# Leds.net
KiCad netlist of a schematic drawn in Altium Designer
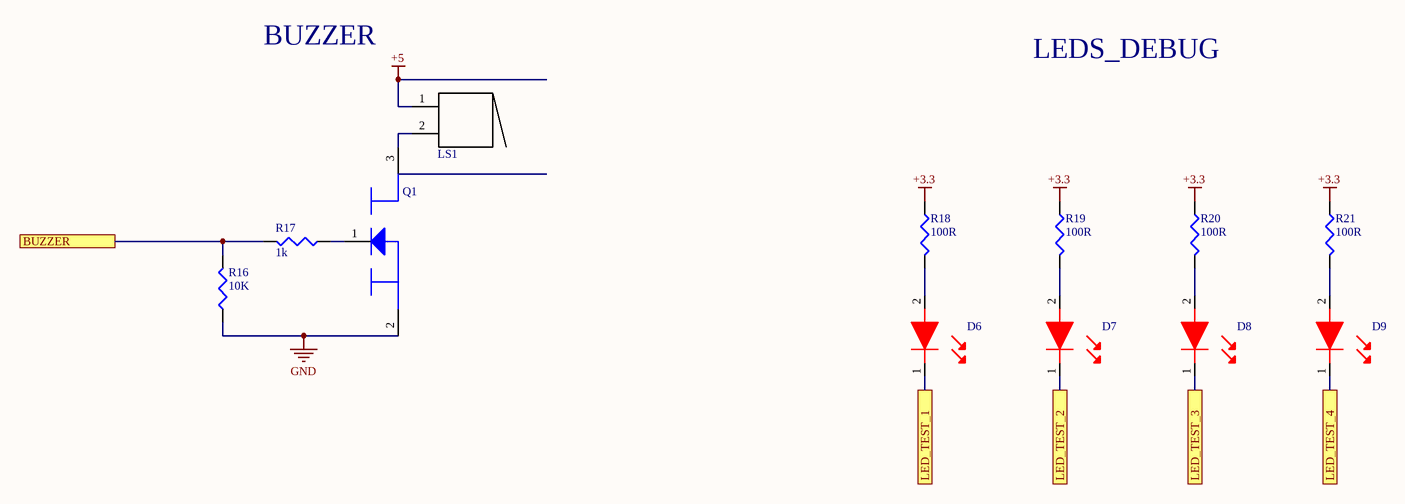
[diagram p0: Leds.SchDoc]

(export (version "E")
  (design (tool "Eeschema 10.0.6"))
  (components
    (comp (ref "D6")
      (value "Standard LEDs - SMD")
      (footprint "Standard LEDs - SMD")
      (description "WURTH ELEKTRONIK - 150060RS75000 - LED, 0603, RED, 250MCD, 625NM")
      (fields
        (field (name "MANUFACTURER") "Wurth Electronics")
        (field (name "MANUFACTURER PART NUMBER") "150060RS75000")
      )
      (libsource (lib "BiricuticoBonito") (part "Standard LEDs - SMD"))
    )
    (comp (ref "D7")
      (value "Standard LEDs - SMD")
      (footprint "Standard LEDs - SMD")
      (description "WURTH ELEKTRONIK - 150060RS75000 - LED, 0603, RED, 250MCD, 625NM")
      (fields
        (field (name "MANUFACTURER") "Wurth Electronics")
        (field (name "MANUFACTURER PART NUMBER") "150060RS75000")
      )
      (libsource (lib "BiricuticoBonito") (part "Standard LEDs - SMD"))
    )
    (comp (ref "D8")
      (value "Standard LEDs - SMD")
      (footprint "Standard LEDs - SMD")
      (description "WURTH ELEKTRONIK - 150060RS75000 - LED, 0603, RED, 250MCD, 625NM")
      (fields
        (field (name "MANUFACTURER") "Wurth Electronics")
        (field (name "MANUFACTURER PART NUMBER") "150060RS75000")
      )
      (libsource (lib "BiricuticoBonito") (part "Standard LEDs - SMD"))
    )
    (comp (ref "D9")
      (value "Standard LEDs - SMD")
      (footprint "Standard LEDs - SMD")
      (description "WURTH ELEKTRONIK - 150060RS75000 - LED, 0603, RED, 250MCD, 625NM")
      (fields
        (field (name "MANUFACTURER") "Wurth Electronics")
        (field (name "MANUFACTURER PART NUMBER") "150060RS75000")
      )
      (libsource (lib "BiricuticoBonito") (part "Standard LEDs - SMD"))
    )
    (comp (ref "LS1")
      (value "Buzzers")
      (footprint "Buzzer")
      (description "Audio 1.1Vp-p 3Vp-p 30mA 1.5Vp-p 85dBA 2400Hz to 2800Hz Through Hole Pin Bulk")
      (fields
        (field (name "MANUFACTURER") "Mallory Sonalert")
        (field (name "MANUFACTURER PART NUMBER") "PB-1226PEAQ")
      )
      (libsource (lib "BiricuticoBonito") (part "Buzzers"))
    )
    (comp (ref "Q1")
      (value "MOSFET")
      (footprint "SOT96P240X110-3N")
      (description "MOSFET N-CH 30V 6.2A SOT23")
      (fields (field (name "MANUFACTURER") "Diodes") (field (name "MANUFACTURER PART NUMBER") "DMN3023L-7"))
      (libsource (lib "BiricuticoBonito") (part "MOSFET"))
    )
    (comp (ref "R16")
      (value "10K")
      (footprint "6-0805_M")
      (description "RES SMD 10K OHM 1% 1/8W 0805")
      (fields
        (field (name "MANUFACTURER") "Vishay")
        (field (name "MANUFACTURER PART NUMBER") "CRCW080510K0FKEA")
      )
      (libsource (lib "BiricuticoBonito") (part "Resistor 10k 0805"))
    )
    (comp (ref "R17")
      (value "1k")
      (footprint "6-0805_M")
      (description "RES SMD 1K OHM 1% 1/8W 0805")
      (fields
        (field (name "MANUFACTURER") "Vishay Dale")
        (field (name "MANUFACTURER PART NUMBER") "CRCW08051K00FKEA")
      )
      (libsource (lib "BiricuticoBonito") (part "Resistor 1K 0805"))
    )
    (comp (ref "R18")
      (value "100R")
      (footprint "0603")
      (description "RES SMD 100 OHM 1% 1/10W 0603")
      (fields
        (field (name "MANUFACTURER") "Vishay Intertechnology")
        (field (name "MANUFACTURER PART NUMBER") "CRCW0603100RFKEA")
      )
      (libsource (lib "BiricuticoBonito") (part "Resistor 100 0603"))
    )
    (comp (ref "R19")
      (value "100R")
      (footprint "0603")
      (description "RES SMD 100 OHM 1% 1/10W 0603")
      (fields
        (field (name "MANUFACTURER") "Vishay Intertechnology")
        (field (name "MANUFACTURER PART NUMBER") "CRCW0603100RFKEA")
      )
      (libsource (lib "BiricuticoBonito") (part "Resistor 100 0603"))
    )
    (comp (ref "R20")
      (value "100R")
      (footprint "0603")
      (description "RES SMD 100 OHM 1% 1/10W 0603")
      (fields
        (field (name "MANUFACTURER") "Vishay Intertechnology")
        (field (name "MANUFACTURER PART NUMBER") "CRCW0603100RFKEA")
      )
      (libsource (lib "BiricuticoBonito") (part "Resistor 100 0603"))
    )
    (comp (ref "R21")
      (value "100R")
      (footprint "0603")
      (description "RES SMD 100 OHM 1% 1/10W 0603")
      (fields
        (field (name "MANUFACTURER") "Vishay Intertechnology")
        (field (name "MANUFACTURER PART NUMBER") "CRCW0603100RFKEA")
      )
      (libsource (lib "BiricuticoBonito") (part "Resistor 100 0603"))
    )
  )
  (nets
    (net (code "1") (name "+3.3") (class "Default")
      (node (ref "R18") (pin "1") (pinfunction "28_1") (pintype "passive"))
      (node (ref "R19") (pin "1") (pinfunction "28_1") (pintype "passive"))
      (node (ref "R20") (pin "1") (pinfunction "28_1") (pintype "passive"))
      (node (ref "R21") (pin "1") (pinfunction "28_1") (pintype "passive"))
    )
    (net (code "2") (name "+5") (class "Default")
      (node (ref "LS1") (pin "1") (pinfunction "20_1") (pintype "passive"))
    )
    (net (code "3") (name "/BUZZER") (class "Default")
      (node (ref "R16") (pin "2") (pinfunction "27_2") (pintype "passive"))
      (node (ref "R17") (pin "2") (pinfunction "27_2") (pintype "passive"))
    )
    (net (code "4") (name "/LED_TEST_1") (class "Default")
      (node (ref "D6") (pin "1") (pinfunction "19_1") (pintype "passive"))
    )
    (net (code "5") (name "/LED_TEST_2") (class "Default")
      (node (ref "D7") (pin "1") (pinfunction "19_1") (pintype "passive"))
    )
    (net (code "6") (name "/LED_TEST_3") (class "Default")
      (node (ref "D8") (pin "1") (pinfunction "19_1") (pintype "passive"))
    )
    (net (code "7") (name "/LED_TEST_4") (class "Default")
      (node (ref "D9") (pin "1") (pinfunction "19_1") (pintype "passive"))
    )
    (net (code "8") (name "GND") (class "Default")
      (node (ref "Q1") (pin "2") (pinfunction "26_2") (pintype "passive"))
      (node (ref "R16") (pin "1") (pinfunction "28_1") (pintype "passive"))
    )
    (net (code "9") (name "Net-(D6-18)") (class "Default")
      (node (ref "D6") (pin "2") (pinfunction "18_2") (pintype "passive"))
      (node (ref "R18") (pin "2") (pinfunction "27_2") (pintype "passive"))
    )
    (net (code "10") (name "Net-(D7-18)") (class "Default")
      (node (ref "D7") (pin "2") (pinfunction "18_2") (pintype "passive"))
      (node (ref "R19") (pin "2") (pinfunction "27_2") (pintype "passive"))
    )
    (net (code "11") (name "Net-(D8-18)") (class "Default")
      (node (ref "D8") (pin "2") (pinfunction "18_2") (pintype "passive"))
      (node (ref "R20") (pin "2") (pinfunction "27_2") (pintype "passive"))
    )
    (net (code "12") (name "Net-(D9-18)") (class "Default")
      (node (ref "D9") (pin "2") (pinfunction "18_2") (pintype "passive"))
      (node (ref "R21") (pin "2") (pinfunction "27_2") (pintype "passive"))
    )
    (net (code "13") (name "Net-(LS1-21)") (class "Default")
      (node (ref "LS1") (pin "2") (pinfunction "21_2") (pintype "passive"))
      (node (ref "Q1") (pin "3") (pinfunction "25_3") (pintype "passive"))
    )
    (net (code "14") (name "Net-(Q1-24)") (class "Default")
      (node (ref "Q1") (pin "1") (pinfunction "24_1") (pintype "passive"))
      (node (ref "R17") (pin "1") (pinfunction "28_1") (pintype "passive"))
    )
  )
)
